# hp3547DisplayV2.net
KiCad netlist of a schematic drawn in EAGLE
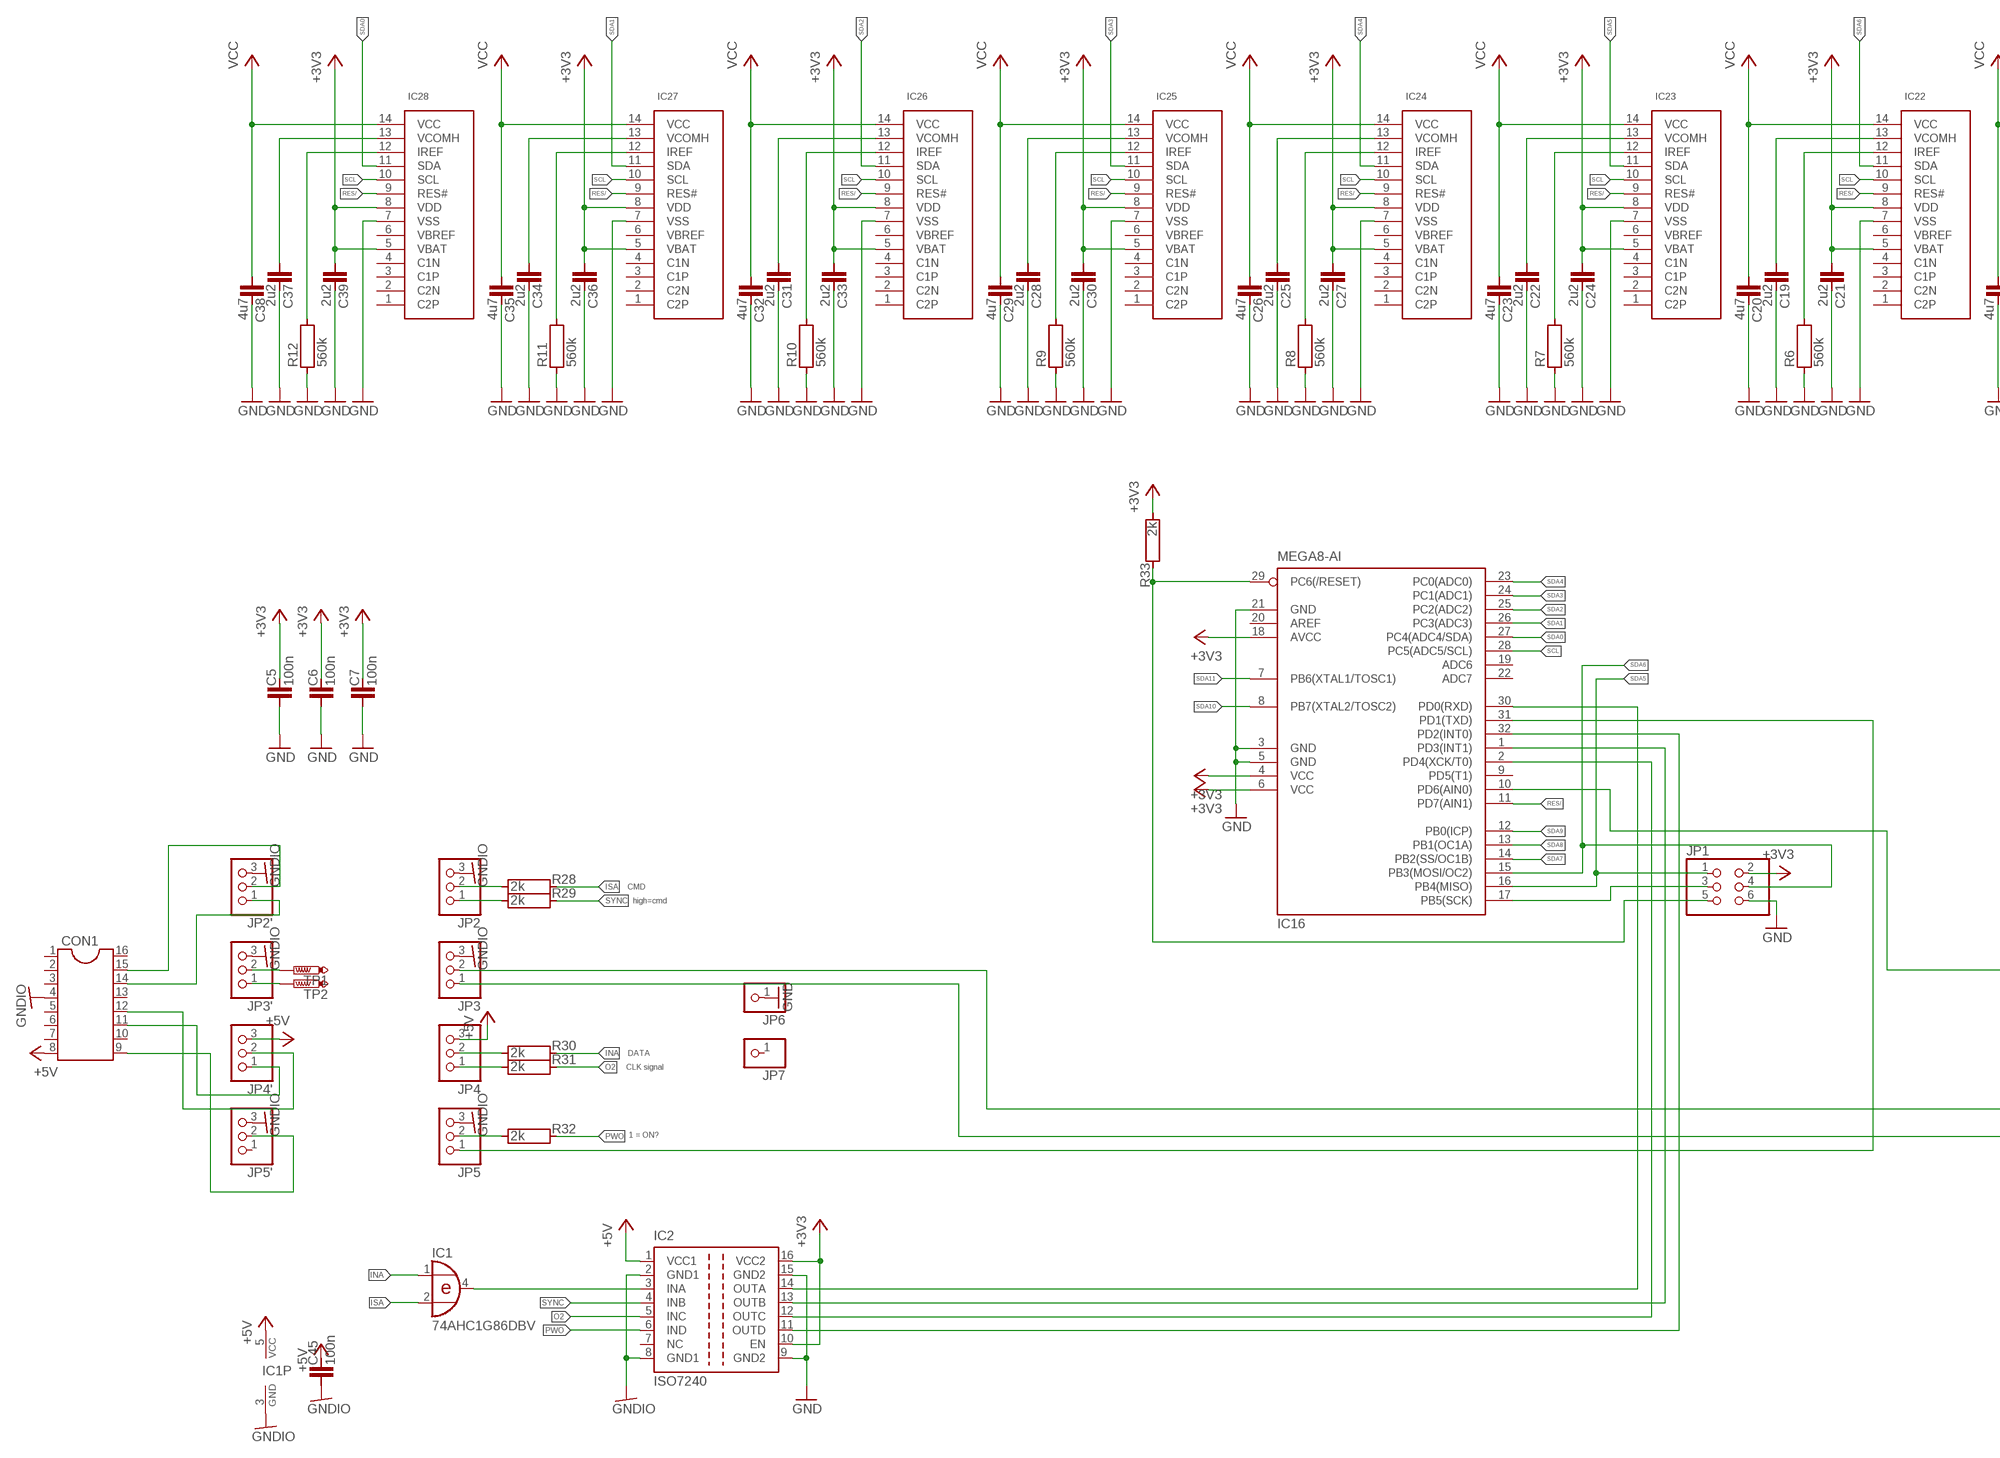
[diagram p0: schematic, sheet 1, part 1 of 2]
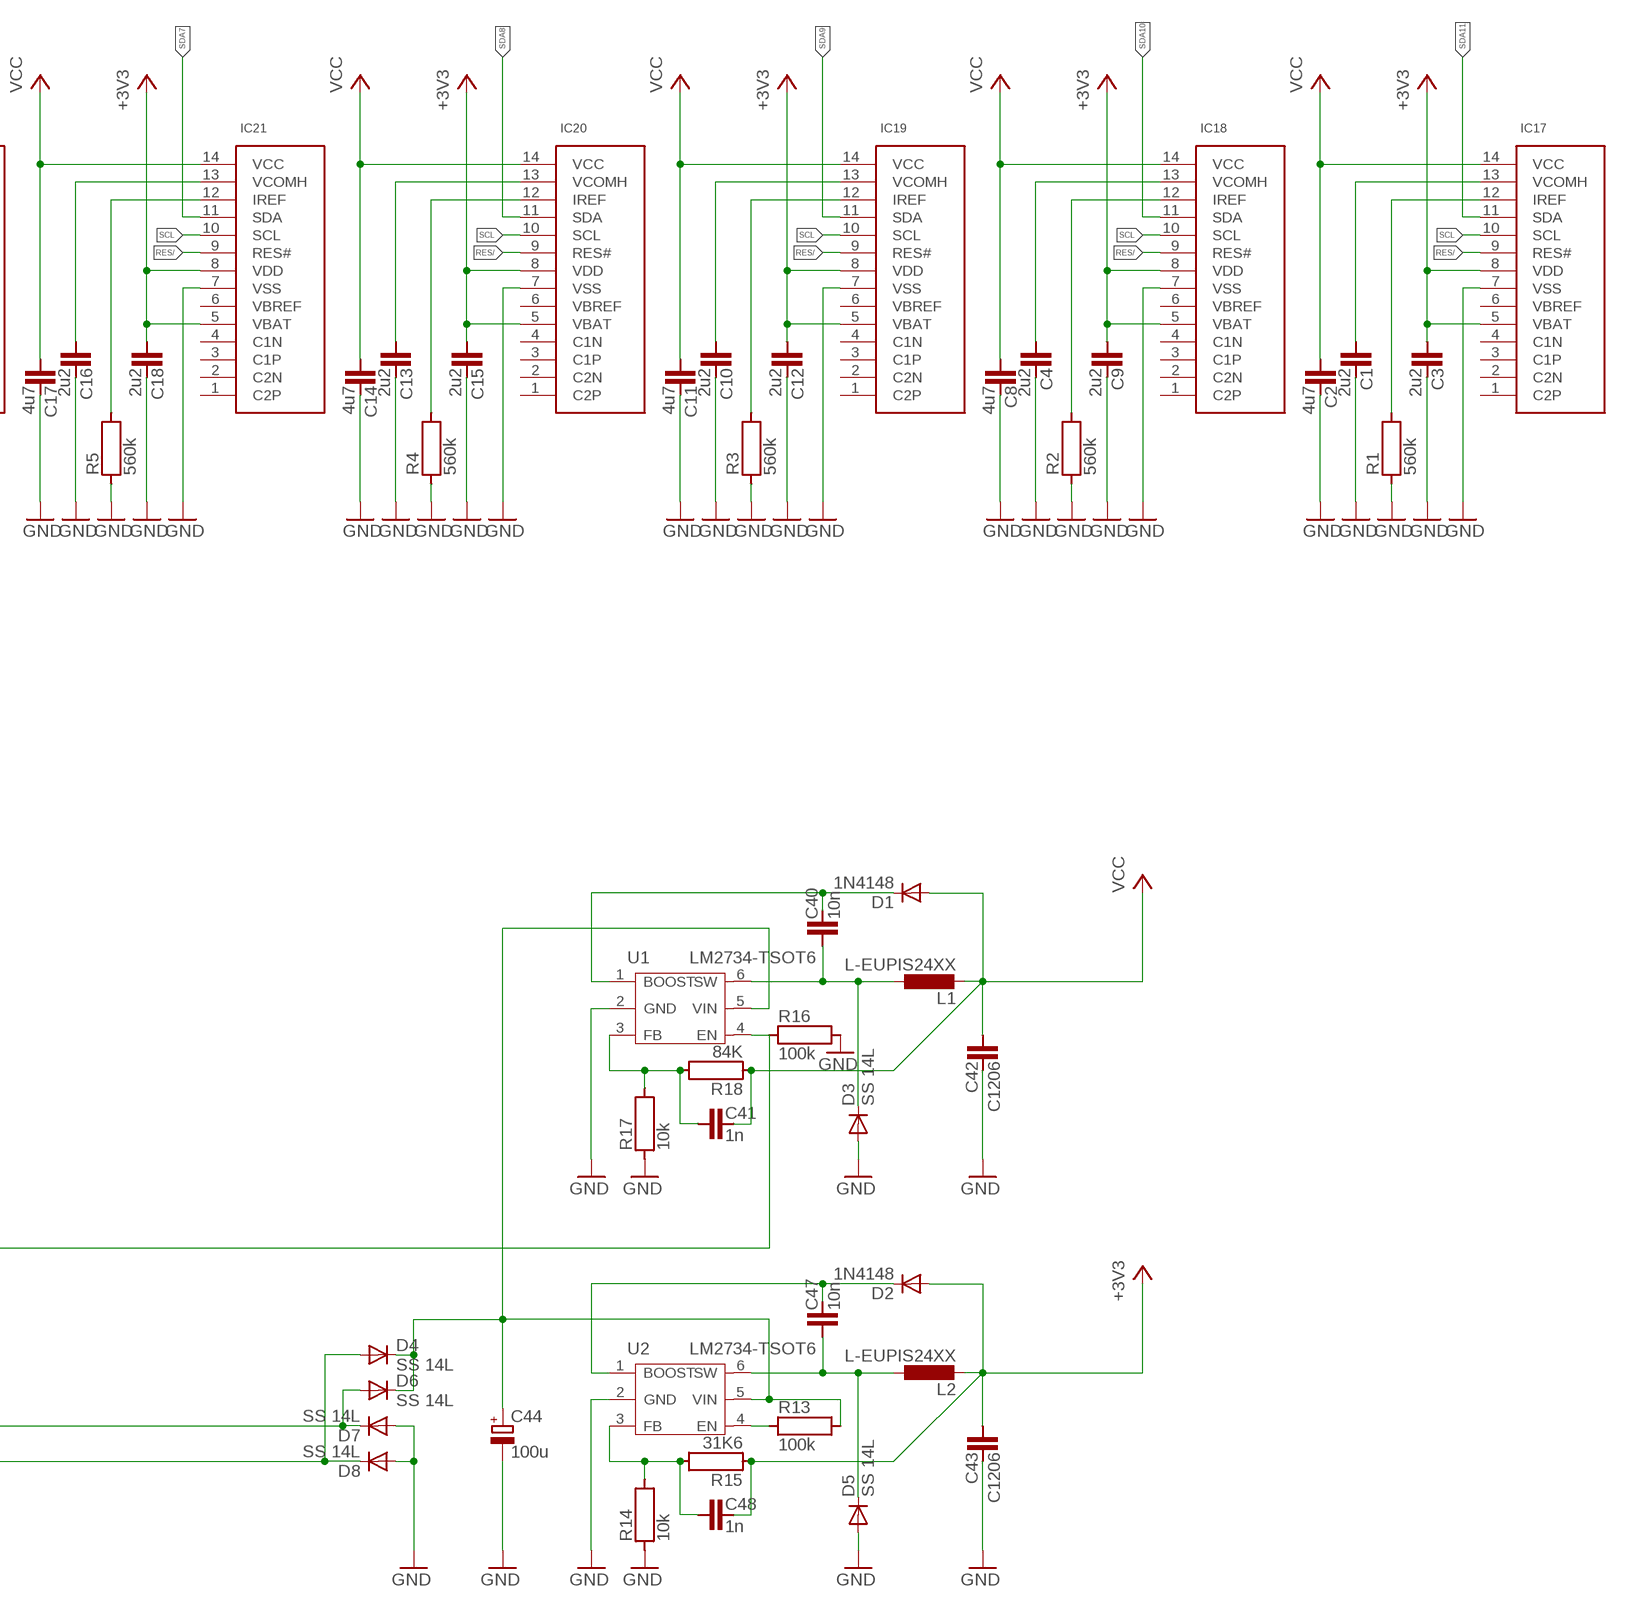
[diagram p1: schematic, sheet 1, part 2 of 2]

(export (version "E")
  (design (tool "Eeschema 10.0.6"))
  (components
    (comp (ref "C1")
      (value "2u2")
      (footprint "eagle-import:C0603")
      (libsource (lib "eagle-import") (part "C0603"))
    )
    (comp (ref "C2")
      (value "4u7")
      (footprint "eagle-import:C0805")
      (libsource (lib "eagle-import") (part "C0805"))
    )
    (comp (ref "C3")
      (value "2u2")
      (footprint "eagle-import:C0603")
      (libsource (lib "eagle-import") (part "C0603"))
    )
    (comp (ref "C4")
      (value "2u2")
      (footprint "eagle-import:C0603")
      (libsource (lib "eagle-import") (part "C0603"))
    )
    (comp (ref "C5")
      (value "100n")
      (footprint "eagle-import:C0603")
      (libsource (lib "eagle-import") (part "C0603"))
    )
    (comp (ref "C6")
      (value "100n")
      (footprint "eagle-import:C0603")
      (libsource (lib "eagle-import") (part "C0603"))
    )
    (comp (ref "C7")
      (value "100n")
      (footprint "eagle-import:C0603")
      (libsource (lib "eagle-import") (part "C0603"))
    )
    (comp (ref "C8")
      (value "4u7")
      (footprint "eagle-import:C0805")
      (libsource (lib "eagle-import") (part "C0805"))
    )
    (comp (ref "C9")
      (value "2u2")
      (footprint "eagle-import:C0603")
      (libsource (lib "eagle-import") (part "C0603"))
    )
    (comp (ref "C10")
      (value "2u2")
      (footprint "eagle-import:C0603")
      (libsource (lib "eagle-import") (part "C0603"))
    )
    (comp (ref "C11")
      (value "4u7")
      (footprint "eagle-import:C0805")
      (libsource (lib "eagle-import") (part "C0805"))
    )
    (comp (ref "C12")
      (value "2u2")
      (footprint "eagle-import:C0603")
      (libsource (lib "eagle-import") (part "C0603"))
    )
    (comp (ref "C13")
      (value "2u2")
      (footprint "eagle-import:C0603")
      (libsource (lib "eagle-import") (part "C0603"))
    )
    (comp (ref "C14")
      (value "4u7")
      (footprint "eagle-import:C0805")
      (libsource (lib "eagle-import") (part "C0805"))
    )
    (comp (ref "C15")
      (value "2u2")
      (footprint "eagle-import:C0603")
      (libsource (lib "eagle-import") (part "C0603"))
    )
    (comp (ref "C16")
      (value "2u2")
      (footprint "eagle-import:C0603")
      (libsource (lib "eagle-import") (part "C0603"))
    )
    (comp (ref "C17")
      (value "4u7")
      (footprint "eagle-import:C0805")
      (libsource (lib "eagle-import") (part "C0805"))
    )
    (comp (ref "C18")
      (value "2u2")
      (footprint "eagle-import:C0603")
      (libsource (lib "eagle-import") (part "C0603"))
    )
    (comp (ref "C19")
      (value "2u2")
      (footprint "eagle-import:C0603")
      (libsource (lib "eagle-import") (part "C0603"))
    )
    (comp (ref "C20")
      (value "4u7")
      (footprint "eagle-import:C0805")
      (libsource (lib "eagle-import") (part "C0805"))
    )
    (comp (ref "C21")
      (value "2u2")
      (footprint "eagle-import:C0603")
      (libsource (lib "eagle-import") (part "C0603"))
    )
    (comp (ref "C22")
      (value "2u2")
      (footprint "eagle-import:C0603")
      (libsource (lib "eagle-import") (part "C0603"))
    )
    (comp (ref "C23")
      (value "4u7")
      (footprint "eagle-import:C0805")
      (libsource (lib "eagle-import") (part "C0805"))
    )
    (comp (ref "C24")
      (value "2u2")
      (footprint "eagle-import:C0603")
      (libsource (lib "eagle-import") (part "C0603"))
    )
    (comp (ref "C25")
      (value "2u2")
      (footprint "eagle-import:C0603")
      (libsource (lib "eagle-import") (part "C0603"))
    )
    (comp (ref "C26")
      (value "4u7")
      (footprint "eagle-import:C0805")
      (libsource (lib "eagle-import") (part "C0805"))
    )
    (comp (ref "C27")
      (value "2u2")
      (footprint "eagle-import:C0603")
      (libsource (lib "eagle-import") (part "C0603"))
    )
    (comp (ref "C28")
      (value "2u2")
      (footprint "eagle-import:C0603")
      (libsource (lib "eagle-import") (part "C0603"))
    )
    (comp (ref "C29")
      (value "4u7")
      (footprint "eagle-import:C0805")
      (libsource (lib "eagle-import") (part "C0805"))
    )
    (comp (ref "C30")
      (value "2u2")
      (footprint "eagle-import:C0603")
      (libsource (lib "eagle-import") (part "C0603"))
    )
    (comp (ref "C31")
      (value "2u2")
      (footprint "eagle-import:C0603")
      (libsource (lib "eagle-import") (part "C0603"))
    )
    (comp (ref "C32")
      (value "4u7")
      (footprint "eagle-import:C0805")
      (libsource (lib "eagle-import") (part "C0805"))
    )
    (comp (ref "C33")
      (value "2u2")
      (footprint "eagle-import:C0603")
      (libsource (lib "eagle-import") (part "C0603"))
    )
    (comp (ref "C34")
      (value "2u2")
      (footprint "eagle-import:C0603")
      (libsource (lib "eagle-import") (part "C0603"))
    )
    (comp (ref "C35")
      (value "4u7")
      (footprint "eagle-import:C0805")
      (libsource (lib "eagle-import") (part "C0805"))
    )
    (comp (ref "C36")
      (value "2u2")
      (footprint "eagle-import:C0603")
      (libsource (lib "eagle-import") (part "C0603"))
    )
    (comp (ref "C37")
      (value "2u2")
      (footprint "eagle-import:C0603")
      (libsource (lib "eagle-import") (part "C0603"))
    )
    (comp (ref "C38")
      (value "4u7")
      (footprint "eagle-import:C0805")
      (libsource (lib "eagle-import") (part "C0805"))
    )
    (comp (ref "C39")
      (value "2u2")
      (footprint "eagle-import:C0603")
      (libsource (lib "eagle-import") (part "C0603"))
    )
    (comp (ref "C40")
      (value "10n")
      (footprint "eagle-import:C0603")
      (libsource (lib "eagle-import") (part "C0603"))
    )
    (comp (ref "C41")
      (value "1n")
      (footprint "eagle-import:C0603")
      (libsource (lib "eagle-import") (part "C0603"))
    )
    (comp (ref "C42")
      (value "C1206")
      (footprint "eagle-import:C1206")
      (libsource (lib "eagle-import") (part "C1206"))
    )
    (comp (ref "C43")
      (value "C1206")
      (footprint "eagle-import:C1206")
      (libsource (lib "eagle-import") (part "C1206"))
    )
    (comp (ref "C44")
      (value "100u")
      (footprint "eagle-import:PANASONIC_E")
      (libsource (lib "eagle-import") (part "CPOL-EUE"))
    )
    (comp (ref "C45")
      (value "100n")
      (footprint "eagle-import:C0603")
      (libsource (lib "eagle-import") (part "C0603"))
    )
    (comp (ref "C47")
      (value "10n")
      (footprint "eagle-import:C0603")
      (libsource (lib "eagle-import") (part "C0603"))
    )
    (comp (ref "C48")
      (value "1n")
      (footprint "eagle-import:C0603")
      (libsource (lib "eagle-import") (part "C0603"))
    )
    (comp (ref "CON1")
      (value "DIL16BIGHOLE")
      (footprint "eagle-import:DIL16BIGHOLE")
      (libsource (lib "eagle-import") (part "DIL16BIGHOLE"))
    )
    (comp (ref "D1")
      (value "1N4148")
      (footprint "eagle-import:DO214AC")
      (libsource (lib "eagle-import") (part "DIODE-DO214AC"))
    )
    (comp (ref "D2")
      (value "1N4148")
      (footprint "eagle-import:DO214AC")
      (libsource (lib "eagle-import") (part "DIODE-DO214AC"))
    )
    (comp (ref "D3")
      (value "SS 14L")
      (footprint "eagle-import:SOD-123_MINI-SMA")
      (libsource (lib "eagle-import") (part "CGRM400-G1"))
    )
    (comp (ref "D4")
      (value "SS 14L")
      (footprint "eagle-import:SOD-123_MINI-SMA")
      (libsource (lib "eagle-import") (part "CGRM400-G1"))
    )
    (comp (ref "D5")
      (value "SS 14L")
      (footprint "eagle-import:SOD-123_MINI-SMA")
      (libsource (lib "eagle-import") (part "CGRM400-G1"))
    )
    (comp (ref "D6")
      (value "SS 14L")
      (footprint "eagle-import:SOD-123_MINI-SMA")
      (libsource (lib "eagle-import") (part "CGRM400-G1"))
    )
    (comp (ref "D7")
      (value "SS 14L")
      (footprint "eagle-import:SOD-123_MINI-SMA")
      (libsource (lib "eagle-import") (part "CGRM400-G1"))
    )
    (comp (ref "D8")
      (value "SS 14L")
      (footprint "eagle-import:SOD-123_MINI-SMA")
      (libsource (lib "eagle-import") (part "CGRM400-G1"))
    )
    (comp (ref "IC1")
      (value "74AHC1G86DBV")
      (footprint "eagle-import:SOT23-5")
      (libsource (lib "eagle-import") (part "741G86DBVAHC"))
    )
    (comp (ref "IC2")
      (value "ISO7240")
      (footprint "eagle-import:SO-16DW")
      (fields (field (name "MPN") "ISO7240MDW"))
      (libsource (lib "eagle-import") (part "ISO7240"))
    )
    (comp (ref "IC16")
      (value "MEGA8-AI")
      (footprint "eagle-import:TQFP32-08")
      (fields (field (name "MPN") "ATMEGA8-16AU"))
      (libsource (lib "eagle-import") (part "MEGA8-AI"))
    )
    (comp (ref "IC17")
      (value "OLED0.87")
      (footprint "eagle-import:OLED0.87")
      (libsource (lib "eagle-import") (part "OLED0.87"))
    )
    (comp (ref "IC18")
      (value "OLED0.87")
      (footprint "eagle-import:OLED0.87")
      (libsource (lib "eagle-import") (part "OLED0.87"))
    )
    (comp (ref "IC19")
      (value "OLED0.87")
      (footprint "eagle-import:OLED0.87")
      (libsource (lib "eagle-import") (part "OLED0.87"))
    )
    (comp (ref "IC20")
      (value "OLED0.87")
      (footprint "eagle-import:OLED0.87")
      (libsource (lib "eagle-import") (part "OLED0.87"))
    )
    (comp (ref "IC21")
      (value "OLED0.87")
      (footprint "eagle-import:OLED0.87")
      (libsource (lib "eagle-import") (part "OLED0.87"))
    )
    (comp (ref "IC22")
      (value "OLED0.87")
      (footprint "eagle-import:OLED0.87")
      (libsource (lib "eagle-import") (part "OLED0.87"))
    )
    (comp (ref "IC23")
      (value "OLED0.87")
      (footprint "eagle-import:OLED0.87")
      (libsource (lib "eagle-import") (part "OLED0.87"))
    )
    (comp (ref "IC24")
      (value "OLED0.87")
      (footprint "eagle-import:OLED0.87")
      (libsource (lib "eagle-import") (part "OLED0.87"))
    )
    (comp (ref "IC25")
      (value "OLED0.87")
      (footprint "eagle-import:OLED0.87")
      (libsource (lib "eagle-import") (part "OLED0.87"))
    )
    (comp (ref "IC26")
      (value "OLED0.87")
      (footprint "eagle-import:OLED0.87")
      (libsource (lib "eagle-import") (part "OLED0.87"))
    )
    (comp (ref "IC27")
      (value "OLED0.87")
      (footprint "eagle-import:OLED0.87")
      (libsource (lib "eagle-import") (part "OLED0.87"))
    )
    (comp (ref "IC28")
      (value "OLED0.87")
      (footprint "eagle-import:OLED0.87")
      (libsource (lib "eagle-import") (part "OLED0.87"))
    )
    (comp (ref "JP1")
      (value "PINHD-2X3")
      (footprint "eagle-import:2X03")
      (libsource (lib "eagle-import") (part "PINHD-2X3"))
    )
    (comp (ref "JP2")
      (value "PINHD-1X3")
      (footprint "eagle-import:1X03")
      (libsource (lib "eagle-import") (part "PINHD-1X3"))
    )
    (comp (ref "JP2'")
      (value "PINHD-1X3")
      (footprint "eagle-import:1X03")
      (libsource (lib "eagle-import") (part "PINHD-1X3"))
    )
    (comp (ref "JP3")
      (value "PINHD-1X3")
      (footprint "eagle-import:1X03")
      (libsource (lib "eagle-import") (part "PINHD-1X3"))
    )
    (comp (ref "JP3'")
      (value "PINHD-1X3")
      (footprint "eagle-import:1X03")
      (libsource (lib "eagle-import") (part "PINHD-1X3"))
    )
    (comp (ref "JP4")
      (value "PINHD-1X3")
      (footprint "eagle-import:1X03")
      (libsource (lib "eagle-import") (part "PINHD-1X3"))
    )
    (comp (ref "JP4'")
      (value "PINHD-1X3")
      (footprint "eagle-import:1X03")
      (libsource (lib "eagle-import") (part "PINHD-1X3"))
    )
    (comp (ref "JP5")
      (value "PINHD-1X3")
      (footprint "eagle-import:1X03")
      (libsource (lib "eagle-import") (part "PINHD-1X3"))
    )
    (comp (ref "JP5'")
      (value "PINHD-1X3")
      (footprint "eagle-import:1X03")
      (libsource (lib "eagle-import") (part "PINHD-1X3"))
    )
    (comp (ref "JP6")
      (value "PINHD-1X1")
      (footprint "eagle-import:1X01")
      (libsource (lib "eagle-import") (part "PINHD-1X1"))
    )
    (comp (ref "JP7")
      (value "PINHD-1X1")
      (footprint "eagle-import:1X01")
      (libsource (lib "eagle-import") (part "PINHD-1X1"))
    )
    (comp (ref "L1")
      (value "L-EUPIS24XX")
      (footprint "eagle-import:PIS24XX")
      (libsource (lib "eagle-import") (part "L-EUPIS24XX"))
    )
    (comp (ref "L2")
      (value "L-EUPIS24XX")
      (footprint "eagle-import:PIS24XX")
      (libsource (lib "eagle-import") (part "L-EUPIS24XX"))
    )
    (comp (ref "R1")
      (value "560k")
      (footprint "eagle-import:R0402")
      (libsource (lib "eagle-import") (part "R0402"))
    )
    (comp (ref "R2")
      (value "560k")
      (footprint "eagle-import:R0402")
      (libsource (lib "eagle-import") (part "R0402"))
    )
    (comp (ref "R3")
      (value "560k")
      (footprint "eagle-import:R0402")
      (libsource (lib "eagle-import") (part "R0402"))
    )
    (comp (ref "R4")
      (value "560k")
      (footprint "eagle-import:R0402")
      (libsource (lib "eagle-import") (part "R0402"))
    )
    (comp (ref "R5")
      (value "560k")
      (footprint "eagle-import:R0402")
      (libsource (lib "eagle-import") (part "R0402"))
    )
    (comp (ref "R6")
      (value "560k")
      (footprint "eagle-import:R0402")
      (libsource (lib "eagle-import") (part "R0402"))
    )
    (comp (ref "R7")
      (value "560k")
      (footprint "eagle-import:R0402")
      (libsource (lib "eagle-import") (part "R0402"))
    )
    (comp (ref "R8")
      (value "560k")
      (footprint "eagle-import:R0402")
      (libsource (lib "eagle-import") (part "R0402"))
    )
    (comp (ref "R9")
      (value "560k")
      (footprint "eagle-import:R0402")
      (libsource (lib "eagle-import") (part "R0402"))
    )
    (comp (ref "R10")
      (value "560k")
      (footprint "eagle-import:R0402")
      (libsource (lib "eagle-import") (part "R0402"))
    )
    (comp (ref "R11")
      (value "560k")
      (footprint "eagle-import:R0402")
      (libsource (lib "eagle-import") (part "R0402"))
    )
    (comp (ref "R12")
      (value "560k")
      (footprint "eagle-import:R0402")
      (libsource (lib "eagle-import") (part "R0402"))
    )
    (comp (ref "R13")
      (value "100k")
      (footprint "eagle-import:R0603")
      (libsource (lib "eagle-import") (part "R0603"))
    )
    (comp (ref "R14")
      (value "10k")
      (footprint "eagle-import:R0603")
      (libsource (lib "eagle-import") (part "R0603"))
    )
    (comp (ref "R15")
      (value "31K6")
      (footprint "eagle-import:R0603")
      (libsource (lib "eagle-import") (part "R0603"))
    )
    (comp (ref "R16")
      (value "100k")
      (footprint "eagle-import:R0603")
      (libsource (lib "eagle-import") (part "R0603"))
    )
    (comp (ref "R17")
      (value "10k")
      (footprint "eagle-import:R0603")
      (libsource (lib "eagle-import") (part "R0603"))
    )
    (comp (ref "R18")
      (value "84K")
      (footprint "eagle-import:R0603")
      (libsource (lib "eagle-import") (part "R0603"))
    )
    (comp (ref "R28")
      (value "2k")
      (footprint "eagle-import:R0603")
      (libsource (lib "eagle-import") (part "R0603"))
    )
    (comp (ref "R29")
      (value "2k")
      (footprint "eagle-import:R0603")
      (libsource (lib "eagle-import") (part "R0603"))
    )
    (comp (ref "R30")
      (value "2k")
      (footprint "eagle-import:R0603")
      (libsource (lib "eagle-import") (part "R0603"))
    )
    (comp (ref "R31")
      (value "2k")
      (footprint "eagle-import:R0603")
      (libsource (lib "eagle-import") (part "R0603"))
    )
    (comp (ref "R32")
      (value "2k")
      (footprint "eagle-import:R0603")
      (libsource (lib "eagle-import") (part "R0603"))
    )
    (comp (ref "R33")
      (value "2k")
      (footprint "eagle-import:R0603")
      (libsource (lib "eagle-import") (part "R0603"))
    )
    (comp (ref "TP1")
      (value "PTR1PAD1-13Y")
      (footprint "eagle-import:P1-13Y")
      (libsource (lib "eagle-import") (part "PTR1PAD1-13Y"))
    )
    (comp (ref "TP2")
      (value "PTR1PAD1-13Y")
      (footprint "eagle-import:P1-13Y")
      (libsource (lib "eagle-import") (part "PTR1PAD1-13Y"))
    )
    (comp (ref "U1")
      (value "LM2734-TSOT6")
      (footprint "eagle-import:TSOT6")
      (libsource (lib "eagle-import") (part "LM2734-TSOT6"))
    )
    (comp (ref "U2")
      (value "LM2734-TSOT6")
      (footprint "eagle-import:TSOT6")
      (libsource (lib "eagle-import") (part "LM2734-TSOT6"))
    )
  )
  (nets
    (net (code "1") (name "+3V3") (class "Default")
      (node (ref "C12") (pin "1") (pinfunction "1_1") (pintype "passive"))
      (node (ref "C15") (pin "1") (pinfunction "1_1") (pintype "passive"))
      (node (ref "C18") (pin "1") (pinfunction "1_1") (pintype "passive"))
      (node (ref "C21") (pin "1") (pinfunction "1_1") (pintype "passive"))
      (node (ref "C24") (pin "1") (pinfunction "1_1") (pintype "passive"))
      (node (ref "C27") (pin "1") (pinfunction "1_1") (pintype "passive"))
      (node (ref "C3") (pin "1") (pinfunction "1_1") (pintype "passive"))
      (node (ref "C30") (pin "1") (pinfunction "1_1") (pintype "passive"))
      (node (ref "C33") (pin "1") (pinfunction "1_1") (pintype "passive"))
      (node (ref "C36") (pin "1") (pinfunction "1_1") (pintype "passive"))
      (node (ref "C39") (pin "1") (pinfunction "1_1") (pintype "passive"))
      (node (ref "C43") (pin "1") (pinfunction "1_1") (pintype "passive"))
      (node (ref "C48") (pin "2") (pinfunction "2_2") (pintype "passive"))
      (node (ref "C5") (pin "2") (pinfunction "2_2") (pintype "passive"))
      (node (ref "C6") (pin "2") (pinfunction "2_2") (pintype "passive"))
      (node (ref "C7") (pin "2") (pinfunction "2_2") (pintype "passive"))
      (node (ref "C9") (pin "1") (pinfunction "1_1") (pintype "passive"))
      (node (ref "D2") (pin "A") (pinfunction "A_A") (pintype "passive"))
      (node (ref "IC16") (pin "18") (pinfunction "AVCC_18") (pintype "power_in"))
      (node (ref "IC16") (pin "4") (pinfunction "VCC_4") (pintype "power_in"))
      (node (ref "IC16") (pin "6") (pinfunction "VCC_6") (pintype "power_in"))
      (node (ref "IC17") (pin "5") (pinfunction "VBAT_5") (pintype "bidirectional"))
      (node (ref "IC17") (pin "8") (pinfunction "VDD_8") (pintype "bidirectional"))
      (node (ref "IC18") (pin "5") (pinfunction "VBAT_5") (pintype "bidirectional"))
      (node (ref "IC18") (pin "8") (pinfunction "VDD_8") (pintype "bidirectional"))
      (node (ref "IC19") (pin "5") (pinfunction "VBAT_5") (pintype "bidirectional"))
      (node (ref "IC19") (pin "8") (pinfunction "VDD_8") (pintype "bidirectional"))
      (node (ref "IC2") (pin "10") (pinfunction "EN_10") (pintype "input"))
      (node (ref "IC2") (pin "16") (pinfunction "VCC2_16") (pintype "power_in"))
      (node (ref "IC20") (pin "5") (pinfunction "VBAT_5") (pintype "bidirectional"))
      (node (ref "IC20") (pin "8") (pinfunction "VDD_8") (pintype "bidirectional"))
      (node (ref "IC21") (pin "5") (pinfunction "VBAT_5") (pintype "bidirectional"))
      (node (ref "IC21") (pin "8") (pinfunction "VDD_8") (pintype "bidirectional"))
      (node (ref "IC22") (pin "5") (pinfunction "VBAT_5") (pintype "bidirectional"))
      (node (ref "IC22") (pin "8") (pinfunction "VDD_8") (pintype "bidirectional"))
      (node (ref "IC23") (pin "5") (pinfunction "VBAT_5") (pintype "bidirectional"))
      (node (ref "IC23") (pin "8") (pinfunction "VDD_8") (pintype "bidirectional"))
      (node (ref "IC24") (pin "5") (pinfunction "VBAT_5") (pintype "bidirectional"))
      (node (ref "IC24") (pin "8") (pinfunction "VDD_8") (pintype "bidirectional"))
      (node (ref "IC25") (pin "5") (pinfunction "VBAT_5") (pintype "bidirectional"))
      (node (ref "IC25") (pin "8") (pinfunction "VDD_8") (pintype "bidirectional"))
      (node (ref "IC26") (pin "5") (pinfunction "VBAT_5") (pintype "bidirectional"))
      (node (ref "IC26") (pin "8") (pinfunction "VDD_8") (pintype "bidirectional"))
      (node (ref "IC27") (pin "5") (pinfunction "VBAT_5") (pintype "bidirectional"))
      (node (ref "IC27") (pin "8") (pinfunction "VDD_8") (pintype "bidirectional"))
      (node (ref "IC28") (pin "5") (pinfunction "VBAT_5") (pintype "bidirectional"))
      (node (ref "IC28") (pin "8") (pinfunction "VDD_8") (pintype "bidirectional"))
      (node (ref "JP1") (pin "2") (pinfunction "2_2") (pintype "passive"))
      (node (ref "L2") (pin "1") (pinfunction "2_1") (pintype "passive"))
      (node (ref "R15") (pin "1") (pinfunction "1_1") (pintype "passive"))
      (node (ref "R33") (pin "2") (pinfunction "2_2") (pintype "passive"))
    )
    (net (code "2") (name "+5V") (class "Default")
      (node (ref "C45") (pin "2") (pinfunction "2_2") (pintype "passive"))
      (node (ref "CON1") (pin "8") (pinfunction "8_8") (pintype "passive"))
      (node (ref "IC1") (pin "5") (pinfunction "VCC_5") (pintype "power_in"))
      (node (ref "IC2") (pin "1") (pinfunction "VCC1_1") (pintype "power_in"))
      (node (ref "JP4") (pin "3") (pinfunction "3_3") (pintype "passive"))
      (node (ref "JP4'") (pin "3") (pinfunction "3_3") (pintype "passive"))
    )
    (net (code "3") (name "GND") (class "Default")
      (node (ref "C1") (pin "2") (pinfunction "2_2") (pintype "passive"))
      (node (ref "C10") (pin "2") (pinfunction "2_2") (pintype "passive"))
      (node (ref "C11") (pin "2") (pinfunction "2_2") (pintype "passive"))
      (node (ref "C12") (pin "2") (pinfunction "2_2") (pintype "passive"))
      (node (ref "C13") (pin "2") (pinfunction "2_2") (pintype "passive"))
      (node (ref "C14") (pin "2") (pinfunction "2_2") (pintype "passive"))
      (node (ref "C15") (pin "2") (pinfunction "2_2") (pintype "passive"))
      (node (ref "C16") (pin "2") (pinfunction "2_2") (pintype "passive"))
      (node (ref "C17") (pin "2") (pinfunction "2_2") (pintype "passive"))
      (node (ref "C18") (pin "2") (pinfunction "2_2") (pintype "passive"))
      (node (ref "C19") (pin "2") (pinfunction "2_2") (pintype "passive"))
      (node (ref "C2") (pin "2") (pinfunction "2_2") (pintype "passive"))
      (node (ref "C20") (pin "2") (pinfunction "2_2") (pintype "passive"))
      (node (ref "C21") (pin "2") (pinfunction "2_2") (pintype "passive"))
      (node (ref "C22") (pin "2") (pinfunction "2_2") (pintype "passive"))
      (node (ref "C23") (pin "2") (pinfunction "2_2") (pintype "passive"))
      (node (ref "C24") (pin "2") (pinfunction "2_2") (pintype "passive"))
      (node (ref "C25") (pin "2") (pinfunction "2_2") (pintype "passive"))
      (node (ref "C26") (pin "2") (pinfunction "2_2") (pintype "passive"))
      (node (ref "C27") (pin "2") (pinfunction "2_2") (pintype "passive"))
      (node (ref "C28") (pin "2") (pinfunction "2_2") (pintype "passive"))
      (node (ref "C29") (pin "2") (pinfunction "2_2") (pintype "passive"))
      (node (ref "C3") (pin "2") (pinfunction "2_2") (pintype "passive"))
      (node (ref "C30") (pin "2") (pinfunction "2_2") (pintype "passive"))
      (node (ref "C31") (pin "2") (pinfunction "2_2") (pintype "passive"))
      (node (ref "C32") (pin "2") (pinfunction "2_2") (pintype "passive"))
      (node (ref "C33") (pin "2") (pinfunction "2_2") (pintype "passive"))
      (node (ref "C34") (pin "2") (pinfunction "2_2") (pintype "passive"))
      (node (ref "C35") (pin "2") (pinfunction "2_2") (pintype "passive"))
      (node (ref "C36") (pin "2") (pinfunction "2_2") (pintype "passive"))
      (node (ref "C37") (pin "2") (pinfunction "2_2") (pintype "passive"))
      (node (ref "C38") (pin "2") (pinfunction "2_2") (pintype "passive"))
      (node (ref "C39") (pin "2") (pinfunction "2_2") (pintype "passive"))
      (node (ref "C4") (pin "2") (pinfunction "2_2") (pintype "passive"))
      (node (ref "C42") (pin "2") (pinfunction "2_2") (pintype "passive"))
      (node (ref "C43") (pin "2") (pinfunction "2_2") (pintype "passive"))
      (node (ref "C44") (pin "-") (pinfunction "-_-") (pintype "passive"))
      (node (ref "C5") (pin "1") (pinfunction "1_1") (pintype "passive"))
      (node (ref "C6") (pin "1") (pinfunction "1_1") (pintype "passive"))
      (node (ref "C7") (pin "1") (pinfunction "1_1") (pintype "passive"))
      (node (ref "C8") (pin "2") (pinfunction "2_2") (pintype "passive"))
      (node (ref "C9") (pin "2") (pinfunction "2_2") (pintype "passive"))
      (node (ref "D3") (pin "A") (pinfunction "A_A") (pintype "passive"))
      (node (ref "D5") (pin "A") (pinfunction "A_A") (pintype "passive"))
      (node (ref "D7") (pin "A") (pinfunction "A_A") (pintype "passive"))
      (node (ref "D8") (pin "A") (pinfunction "A_A") (pintype "passive"))
      (node (ref "IC16") (pin "21") (pinfunction "GND_21") (pintype "power_in"))
      (node (ref "IC16") (pin "3") (pinfunction "GND_3") (pintype "power_in"))
      (node (ref "IC16") (pin "5") (pinfunction "GND_5") (pintype "power_in"))
      (node (ref "IC17") (pin "7") (pinfunction "VSS_7") (pintype "bidirectional"))
      (node (ref "IC18") (pin "7") (pinfunction "VSS_7") (pintype "bidirectional"))
      (node (ref "IC19") (pin "7") (pinfunction "VSS_7") (pintype "bidirectional"))
      (node (ref "IC2") (pin "15") (pinfunction "GND2_15") (pintype "power_in"))
      (node (ref "IC2") (pin "9") (pinfunction "GND2_9") (pintype "power_in"))
      (node (ref "IC20") (pin "7") (pinfunction "VSS_7") (pintype "bidirectional"))
      (node (ref "IC21") (pin "7") (pinfunction "VSS_7") (pintype "bidirectional"))
      (node (ref "IC22") (pin "7") (pinfunction "VSS_7") (pintype "bidirectional"))
      (node (ref "IC23") (pin "7") (pinfunction "VSS_7") (pintype "bidirectional"))
      (node (ref "IC24") (pin "7") (pinfunction "VSS_7") (pintype "bidirectional"))
      (node (ref "IC25") (pin "7") (pinfunction "VSS_7") (pintype "bidirectional"))
      (node (ref "IC26") (pin "7") (pinfunction "VSS_7") (pintype "bidirectional"))
      (node (ref "IC27") (pin "7") (pinfunction "VSS_7") (pintype "bidirectional"))
      (node (ref "IC28") (pin "7") (pinfunction "VSS_7") (pintype "bidirectional"))
      (node (ref "JP1") (pin "6") (pinfunction "6_6") (pintype "passive"))
      (node (ref "JP6") (pin "1") (pinfunction "1_1") (pintype "passive"))
      (node (ref "R1") (pin "1") (pinfunction "1_1") (pintype "passive"))
      (node (ref "R10") (pin "1") (pinfunction "1_1") (pintype "passive"))
      (node (ref "R11") (pin "1") (pinfunction "1_1") (pintype "passive"))
      (node (ref "R12") (pin "1") (pinfunction "1_1") (pintype "passive"))
      (node (ref "R14") (pin "1") (pinfunction "1_1") (pintype "passive"))
      (node (ref "R16") (pin "2") (pinfunction "2_2") (pintype "passive"))
      (node (ref "R17") (pin "1") (pinfunction "1_1") (pintype "passive"))
      (node (ref "R2") (pin "1") (pinfunction "1_1") (pintype "passive"))
      (node (ref "R3") (pin "1") (pinfunction "1_1") (pintype "passive"))
      (node (ref "R4") (pin "1") (pinfunction "1_1") (pintype "passive"))
      (node (ref "R5") (pin "1") (pinfunction "1_1") (pintype "passive"))
      (node (ref "R6") (pin "1") (pinfunction "1_1") (pintype "passive"))
      (node (ref "R7") (pin "1") (pinfunction "1_1") (pintype "passive"))
      (node (ref "R8") (pin "1") (pinfunction "1_1") (pintype "passive"))
      (node (ref "R9") (pin "1") (pinfunction "1_1") (pintype "passive"))
      (node (ref "U1") (pin "2") (pinfunction "GND_2") (pintype "power_in"))
      (node (ref "U2") (pin "2") (pinfunction "GND_2") (pintype "power_in"))
    )
    (net (code "4") (name "GNDIO") (class "Default")
      (node (ref "C45") (pin "1") (pinfunction "1_1") (pintype "passive"))
      (node (ref "CON1") (pin "4") (pinfunction "4_4") (pintype "passive"))
      (node (ref "IC1") (pin "3") (pinfunction "GND_3") (pintype "power_in"))
      (node (ref "IC2") (pin "2") (pinfunction "GND1_2") (pintype "power_in"))
      (node (ref "IC2") (pin "8") (pinfunction "GND1_8") (pintype "power_in"))
      (node (ref "JP2") (pin "3") (pinfunction "3_3") (pintype "passive"))
      (node (ref "JP2'") (pin "3") (pinfunction "3_3") (pintype "passive"))
      (node (ref "JP3") (pin "3") (pinfunction "3_3") (pintype "passive"))
      (node (ref "JP3'") (pin "3") (pinfunction "3_3") (pintype "passive"))
      (node (ref "JP5") (pin "3") (pinfunction "3_3") (pintype "passive"))
      (node (ref "JP5'") (pin "3") (pinfunction "3_3") (pintype "passive"))
    )
    (net (code "5") (name "INA") (class "Default")
      (node (ref "IC1") (pin "1") (pinfunction "I0_1") (pintype "input"))
      (node (ref "R30") (pin "1") (pinfunction "1_1") (pintype "passive"))
    )
    (net (code "6") (name "ISA") (class "Default")
      (node (ref "IC1") (pin "2") (pinfunction "I1_2") (pintype "input"))
      (node (ref "R28") (pin "1") (pinfunction "1_1") (pintype "passive"))
    )
    (net (code "7") (name "Net-(CON1-Pad9)") (class "Default")
      (node (ref "CON1") (pin "9") (pinfunction "9_9") (pintype "passive"))
      (node (ref "JP5'") (pin "2") (pinfunction "2_2") (pintype "passive"))
    )
    (net (code "8") (name "Net-(CON1-Pad11)") (class "Default")
      (node (ref "CON1") (pin "11") (pinfunction "11_11") (pintype "passive"))
      (node (ref "JP4'") (pin "1") (pinfunction "1_1") (pintype "passive"))
    )
    (net (code "9") (name "Net-(CON1-Pad12)") (class "Default")
      (node (ref "CON1") (pin "12") (pinfunction "12_12") (pintype "passive"))
      (node (ref "JP4'") (pin "2") (pinfunction "2_2") (pintype "passive"))
    )
    (net (code "10") (name "Net-(CON1-Pad14)") (class "Default")
      (node (ref "CON1") (pin "14") (pinfunction "14_14") (pintype "passive"))
      (node (ref "JP2'") (pin "1") (pinfunction "1_1") (pintype "passive"))
    )
    (net (code "11") (name "Net-(CON1-Pad15)") (class "Default")
      (node (ref "CON1") (pin "15") (pinfunction "15_15") (pintype "passive"))
      (node (ref "JP2'") (pin "2") (pinfunction "2_2") (pintype "passive"))
    )
    (net (code "12") (name "Net-(D4-PadA)") (class "Default")
      (node (ref "D4") (pin "A") (pinfunction "A_A") (pintype "passive"))
      (node (ref "D8") (pin "C") (pinfunction "C_C") (pintype "passive"))
      (node (ref "JP3") (pin "1") (pinfunction "1_1") (pintype "passive"))
    )
    (net (code "13") (name "Net-(D6-PadA)") (class "Default")
      (node (ref "D6") (pin "A") (pinfunction "A_A") (pintype "passive"))
      (node (ref "D7") (pin "C") (pinfunction "C_C") (pintype "passive"))
      (node (ref "JP3") (pin "2") (pinfunction "2_2") (pintype "passive"))
    )
    (net (code "14") (name "Net-(IC1A-O)") (class "Default")
      (node (ref "IC1") (pin "4") (pinfunction "O_4") (pintype "output"))
      (node (ref "IC2") (pin "3") (pinfunction "INA_3") (pintype "input"))
    )
    (net (code "15") (name "Net-(IC16-PB5(SCK))") (class "Default")
      (node (ref "IC16") (pin "17") (pinfunction "PB5(SCK)_17") (pintype "bidirectional"))
      (node (ref "JP1") (pin "3") (pinfunction "3_3") (pintype "passive"))
    )
    (net (code "16") (name "Net-(IC16-PC6({slash}RESET))") (class "Default")
      (node (ref "IC16") (pin "29") (pinfunction "PC6(/RESET)_29") (pintype "bidirectional"))
      (node (ref "JP1") (pin "5") (pinfunction "5_5") (pintype "passive"))
      (node (ref "R33") (pin "1") (pinfunction "1_1") (pintype "passive"))
    )
    (net (code "17") (name "Net-(IC16-PD0(RXD))") (class "Default")
      (node (ref "IC16") (pin "30") (pinfunction "PD0(RXD)_30") (pintype "bidirectional"))
      (node (ref "IC2") (pin "14") (pinfunction "OUTA_14") (pintype "output"))
    )
    (net (code "18") (name "Net-(IC16-PD1(TXD))") (class "Default")
      (node (ref "IC16") (pin "31") (pinfunction "PD1(TXD)_31") (pintype "bidirectional"))
      (node (ref "JP5") (pin "1") (pinfunction "1_1") (pintype "passive"))
    )
    (net (code "19") (name "Net-(IC16-PD2(INT0))") (class "Default")
      (node (ref "IC16") (pin "32") (pinfunction "PD2(INT0)_32") (pintype "bidirectional"))
      (node (ref "IC2") (pin "11") (pinfunction "OUTD_11") (pintype "output"))
    )
    (net (code "20") (name "Net-(IC16-PD3(INT1))") (class "Default")
      (node (ref "IC16") (pin "1") (pinfunction "PD3(INT1)_1") (pintype "bidirectional"))
      (node (ref "IC2") (pin "13") (pinfunction "OUTB_13") (pintype "output"))
    )
    (net (code "21") (name "Net-(IC16-PD4(XCK{slash}T0))") (class "Default")
      (node (ref "IC16") (pin "2") (pinfunction "PD4(XCK/T0)_2") (pintype "bidirectional"))
      (node (ref "IC2") (pin "12") (pinfunction "OUTC_12") (pintype "output"))
    )
    (net (code "22") (name "Net-(IC16-PD6(AIN0))") (class "Default")
      (node (ref "IC16") (pin "10") (pinfunction "PD6(AIN0)_10") (pintype "bidirectional"))
      (node (ref "R16") (pin "1") (pinfunction "1_1") (pintype "passive"))
      (node (ref "U1") (pin "4") (pinfunction "EN_4") (pintype "input"))
    )
    (net (code "23") (name "Net-(IC17-IREF)") (class "Default")
      (node (ref "IC17") (pin "12") (pinfunction "IREF_12") (pintype "bidirectional"))
      (node (ref "R1") (pin "2") (pinfunction "2_2") (pintype "passive"))
    )
    (net (code "24") (name "Net-(IC17-VCOMH)") (class "Default")
      (node (ref "C1") (pin "1") (pinfunction "1_1") (pintype "passive"))
      (node (ref "IC17") (pin "13") (pinfunction "VCOMH_13") (pintype "bidirectional"))
    )
    (net (code "25") (name "Net-(IC18-IREF)") (class "Default")
      (node (ref "IC18") (pin "12") (pinfunction "IREF_12") (pintype "bidirectional"))
      (node (ref "R2") (pin "2") (pinfunction "2_2") (pintype "passive"))
    )
    (net (code "26") (name "Net-(IC18-VCOMH)") (class "Default")
      (node (ref "C4") (pin "1") (pinfunction "1_1") (pintype "passive"))
      (node (ref "IC18") (pin "13") (pinfunction "VCOMH_13") (pintype "bidirectional"))
    )
    (net (code "27") (name "Net-(IC19-IREF)") (class "Default")
      (node (ref "IC19") (pin "12") (pinfunction "IREF_12") (pintype "bidirectional"))
      (node (ref "R3") (pin "2") (pinfunction "2_2") (pintype "passive"))
    )
    (net (code "28") (name "Net-(IC19-VCOMH)") (class "Default")
      (node (ref "C10") (pin "1") (pinfunction "1_1") (pintype "passive"))
      (node (ref "IC19") (pin "13") (pinfunction "VCOMH_13") (pintype "bidirectional"))
    )
    (net (code "29") (name "Net-(IC20-IREF)") (class "Default")
      (node (ref "IC20") (pin "12") (pinfunction "IREF_12") (pintype "bidirectional"))
      (node (ref "R4") (pin "2") (pinfunction "2_2") (pintype "passive"))
    )
    (net (code "30") (name "Net-(IC20-VCOMH)") (class "Default")
      (node (ref "C13") (pin "1") (pinfunction "1_1") (pintype "passive"))
      (node (ref "IC20") (pin "13") (pinfunction "VCOMH_13") (pintype "bidirectional"))
    )
    (net (code "31") (name "Net-(IC21-IREF)") (class "Default")
      (node (ref "IC21") (pin "12") (pinfunction "IREF_12") (pintype "bidirectional"))
      (node (ref "R5") (pin "2") (pinfunction "2_2") (pintype "passive"))
    )
    (net (code "32") (name "Net-(IC21-VCOMH)") (class "Default")
      (node (ref "C16") (pin "1") (pinfunction "1_1") (pintype "passive"))
      (node (ref "IC21") (pin "13") (pinfunction "VCOMH_13") (pintype "bidirectional"))
    )
    (net (code "33") (name "Net-(IC22-IREF)") (class "Default")
      (node (ref "IC22") (pin "12") (pinfunction "IREF_12") (pintype "bidirectional"))
      (node (ref "R6") (pin "2") (pinfunction "2_2") (pintype "passive"))
    )
    (net (code "34") (name "Net-(IC22-VCOMH)") (class "Default")
      (node (ref "C19") (pin "1") (pinfunction "1_1") (pintype "passive"))
      (node (ref "IC22") (pin "13") (pinfunction "VCOMH_13") (pintype "bidirectional"))
    )
    (net (code "35") (name "Net-(IC23-IREF)") (class "Default")
      (node (ref "IC23") (pin "12") (pinfunction "IREF_12") (pintype "bidirectional"))
      (node (ref "R7") (pin "2") (pinfunction "2_2") (pintype "passive"))
    )
    (net (code "36") (name "Net-(IC23-VCOMH)") (class "Default")
      (node (ref "C22") (pin "1") (pinfunction "1_1") (pintype "passive"))
      (node (ref "IC23") (pin "13") (pinfunction "VCOMH_13") (pintype "bidirectional"))
    )
    (net (code "37") (name "Net-(IC24-IREF)") (class "Default")
      (node (ref "IC24") (pin "12") (pinfunction "IREF_12") (pintype "bidirectional"))
      (node (ref "R8") (pin "2") (pinfunction "2_2") (pintype "passive"))
    )
    (net (code "38") (name "Net-(IC24-VCOMH)") (class "Default")
      (node (ref "C25") (pin "1") (pinfunction "1_1") (pintype "passive"))
      (node (ref "IC24") (pin "13") (pinfunction "VCOMH_13") (pintype "bidirectional"))
    )
    (net (code "39") (name "Net-(IC25-IREF)") (class "Default")
      (node (ref "IC25") (pin "12") (pinfunction "IREF_12") (pintype "bidirectional"))
      (node (ref "R9") (pin "2") (pinfunction "2_2") (pintype "passive"))
    )
    (net (code "40") (name "Net-(IC25-VCOMH)") (class "Default")
      (node (ref "C28") (pin "1") (pinfunction "1_1") (pintype "passive"))
      (node (ref "IC25") (pin "13") (pinfunction "VCOMH_13") (pintype "bidirectional"))
    )
    (net (code "41") (name "Net-(IC26-IREF)") (class "Default")
      (node (ref "IC26") (pin "12") (pinfunction "IREF_12") (pintype "bidirectional"))
      (node (ref "R10") (pin "2") (pinfunction "2_2") (pintype "passive"))
    )
    (net (code "42") (name "Net-(IC26-VCOMH)") (class "Default")
      (node (ref "C31") (pin "1") (pinfunction "1_1") (pintype "passive"))
      (node (ref "IC26") (pin "13") (pinfunction "VCOMH_13") (pintype "bidirectional"))
    )
    (net (code "43") (name "Net-(IC27-IREF)") (class "Default")
      (node (ref "IC27") (pin "12") (pinfunction "IREF_12") (pintype "bidirectional"))
      (node (ref "R11") (pin "2") (pinfunction "2_2") (pintype "passive"))
    )
    (net (code "44") (name "Net-(IC27-VCOMH)") (class "Default")
      (node (ref "C34") (pin "1") (pinfunction "1_1") (pintype "passive"))
      (node (ref "IC27") (pin "13") (pinfunction "VCOMH_13") (pintype "bidirectional"))
    )
    (net (code "45") (name "Net-(IC28-IREF)") (class "Default")
      (node (ref "IC28") (pin "12") (pinfunction "IREF_12") (pintype "bidirectional"))
      (node (ref "R12") (pin "2") (pinfunction "2_2") (pintype "passive"))
    )
    (net (code "46") (name "Net-(IC28-VCOMH)") (class "Default")
      (node (ref "C37") (pin "1") (pinfunction "1_1") (pintype "passive"))
      (node (ref "IC28") (pin "13") (pinfunction "VCOMH_13") (pintype "bidirectional"))
    )
    (net (code "47") (name "Net-(JP2-Pad1)") (class "Default")
      (node (ref "JP2") (pin "1") (pinfunction "1_1") (pintype "passive"))
      (node (ref "R29") (pin "2") (pinfunction "2_2") (pintype "passive"))
    )
    (net (code "48") (name "Net-(JP2-Pad2)") (class "Default")
      (node (ref "JP2") (pin "2") (pinfunction "2_2") (pintype "passive"))
      (node (ref "R28") (pin "2") (pinfunction "2_2") (pintype "passive"))
    )
    (net (code "49") (name "Net-(JP3'-Pad1)") (class "Default")
      (node (ref "JP3'") (pin "1") (pinfunction "1_1") (pintype "passive"))
      (node (ref "TP2") (pin "TP") (pinfunction "TP_TP") (pintype "input"))
    )
    (net (code "50") (name "Net-(JP3'-Pad2)") (class "Default")
      (node (ref "JP3'") (pin "2") (pinfunction "2_2") (pintype "passive"))
      (node (ref "TP1") (pin "TP") (pinfunction "TP_TP") (pintype "input"))
    )
    (net (code "51") (name "Net-(JP4-Pad1)") (class "Default")
      (node (ref "JP4") (pin "1") (pinfunction "1_1") (pintype "passive"))
      (node (ref "R31") (pin "2") (pinfunction "2_2") (pintype "passive"))
    )
    (net (code "52") (name "Net-(JP4-Pad2)") (class "Default")
      (node (ref "JP4") (pin "2") (pinfunction "2_2") (pintype "passive"))
      (node (ref "R30") (pin "2") (pinfunction "2_2") (pintype "passive"))
    )
    (net (code "53") (name "Net-(JP5-Pad2)") (class "Default")
      (node (ref "JP5") (pin "2") (pinfunction "2_2") (pintype "passive"))
      (node (ref "R32") (pin "2") (pinfunction "2_2") (pintype "passive"))
    )
    (net (code "54") (name "Net-(L1-1)") (class "Default")
      (node (ref "C40") (pin "1") (pinfunction "1_1") (pintype "passive"))
      (node (ref "D3") (pin "C") (pinfunction "C_C") (pintype "passive"))
      (node (ref "L1") (pin "2") (pinfunction "1_2") (pintype "passive"))
      (node (ref "U1") (pin "6") (pinfunction "SW_6") (pintype "output"))
    )
    (net (code "55") (name "Net-(L2-1)") (class "Default")
      (node (ref "C47") (pin "1") (pinfunction "1_1") (pintype "passive"))
      (node (ref "D5") (pin "C") (pinfunction "C_C") (pintype "passive"))
      (node (ref "L2") (pin "2") (pinfunction "1_2") (pintype "passive"))
      (node (ref "U2") (pin "6") (pinfunction "SW_6") (pintype "output"))
    )
    (net (code "56") (name "Net-(U1-BOOST)") (class "Default")
      (node (ref "C40") (pin "2") (pinfunction "2_2") (pintype "passive"))
      (node (ref "D1") (pin "C") (pinfunction "C_C") (pintype "passive"))
      (node (ref "U1") (pin "1") (pinfunction "BOOST_1") (pintype "input"))
    )
    (net (code "57") (name "Net-(U1-FB)") (class "Default")
      (node (ref "C41") (pin "1") (pinfunction "1_1") (pintype "passive"))
      (node (ref "R17") (pin "2") (pinfunction "2_2") (pintype "passive"))
      (node (ref "R18") (pin "2") (pinfunction "2_2") (pintype "passive"))
      (node (ref "U1") (pin "3") (pinfunction "FB_3") (pintype "input"))
    )
    (net (code "58") (name "Net-(U1-VIN)") (class "Default")
      (node (ref "C44") (pin "+") (pinfunction "+_+") (pintype "passive"))
      (node (ref "D4") (pin "C") (pinfunction "C_C") (pintype "passive"))
      (node (ref "D6") (pin "C") (pinfunction "C_C") (pintype "passive"))
      (node (ref "R13") (pin "2") (pinfunction "2_2") (pintype "passive"))
      (node (ref "U1") (pin "5") (pinfunction "VIN_5") (pintype "power_in"))
      (node (ref "U2") (pin "5") (pinfunction "VIN_5") (pintype "power_in"))
    )
    (net (code "59") (name "Net-(U2-BOOST)") (class "Default")
      (node (ref "C47") (pin "2") (pinfunction "2_2") (pintype "passive"))
      (node (ref "D2") (pin "C") (pinfunction "C_C") (pintype "passive"))
      (node (ref "U2") (pin "1") (pinfunction "BOOST_1") (pintype "input"))
    )
    (net (code "60") (name "Net-(U2-EN)") (class "Default")
      (node (ref "R13") (pin "1") (pinfunction "1_1") (pintype "passive"))
      (node (ref "U2") (pin "4") (pinfunction "EN_4") (pintype "input"))
    )
    (net (code "61") (name "Net-(U2-FB)") (class "Default")
      (node (ref "C48") (pin "1") (pinfunction "1_1") (pintype "passive"))
      (node (ref "R14") (pin "2") (pinfunction "2_2") (pintype "passive"))
      (node (ref "R15") (pin "2") (pinfunction "2_2") (pintype "passive"))
      (node (ref "U2") (pin "3") (pinfunction "FB_3") (pintype "input"))
    )
    (net (code "62") (name "O2") (class "Default")
      (node (ref "IC2") (pin "5") (pinfunction "INC_5") (pintype "input"))
      (node (ref "R31") (pin "1") (pinfunction "1_1") (pintype "passive"))
    )
    (net (code "63") (name "PWO") (class "Default")
      (node (ref "IC2") (pin "6") (pinfunction "IND_6") (pintype "input"))
      (node (ref "R32") (pin "1") (pinfunction "1_1") (pintype "passive"))
    )
    (net (code "64") (name "RES{slash}") (class "Default")
      (node (ref "IC16") (pin "11") (pinfunction "PD7(AIN1)_11") (pintype "bidirectional"))
      (node (ref "IC17") (pin "9") (pinfunction "RES#_9") (pintype "bidirectional"))
      (node (ref "IC18") (pin "9") (pinfunction "RES#_9") (pintype "bidirectional"))
      (node (ref "IC19") (pin "9") (pinfunction "RES#_9") (pintype "bidirectional"))
      (node (ref "IC20") (pin "9") (pinfunction "RES#_9") (pintype "bidirectional"))
      (node (ref "IC21") (pin "9") (pinfunction "RES#_9") (pintype "bidirectional"))
      (node (ref "IC22") (pin "9") (pinfunction "RES#_9") (pintype "bidirectional"))
      (node (ref "IC23") (pin "9") (pinfunction "RES#_9") (pintype "bidirectional"))
      (node (ref "IC24") (pin "9") (pinfunction "RES#_9") (pintype "bidirectional"))
      (node (ref "IC25") (pin "9") (pinfunction "RES#_9") (pintype "bidirectional"))
      (node (ref "IC26") (pin "9") (pinfunction "RES#_9") (pintype "bidirectional"))
      (node (ref "IC27") (pin "9") (pinfunction "RES#_9") (pintype "bidirectional"))
      (node (ref "IC28") (pin "9") (pinfunction "RES#_9") (pintype "bidirectional"))
    )
    (net (code "65") (name "SCL") (class "Default")
      (node (ref "IC16") (pin "28") (pinfunction "PC5(ADC5/SCL)_28") (pintype "bidirectional"))
      (node (ref "IC17") (pin "10") (pinfunction "SCL_10") (pintype "bidirectional"))
      (node (ref "IC18") (pin "10") (pinfunction "SCL_10") (pintype "bidirectional"))
      (node (ref "IC19") (pin "10") (pinfunction "SCL_10") (pintype "bidirectional"))
      (node (ref "IC20") (pin "10") (pinfunction "SCL_10") (pintype "bidirectional"))
      (node (ref "IC21") (pin "10") (pinfunction "SCL_10") (pintype "bidirectional"))
      (node (ref "IC22") (pin "10") (pinfunction "SCL_10") (pintype "bidirectional"))
      (node (ref "IC23") (pin "10") (pinfunction "SCL_10") (pintype "bidirectional"))
      (node (ref "IC24") (pin "10") (pinfunction "SCL_10") (pintype "bidirectional"))
      (node (ref "IC25") (pin "10") (pinfunction "SCL_10") (pintype "bidirectional"))
      (node (ref "IC26") (pin "10") (pinfunction "SCL_10") (pintype "bidirectional"))
      (node (ref "IC27") (pin "10") (pinfunction "SCL_10") (pintype "bidirectional"))
      (node (ref "IC28") (pin "10") (pinfunction "SCL_10") (pintype "bidirectional"))
    )
    (net (code "66") (name "SDA0") (class "Default")
      (node (ref "IC16") (pin "27") (pinfunction "PC4(ADC4/SDA)_27") (pintype "bidirectional"))
      (node (ref "IC28") (pin "11") (pinfunction "SDA_11") (pintype "bidirectional"))
    )
    (net (code "67") (name "SDA1") (class "Default")
      (node (ref "IC16") (pin "26") (pinfunction "PC3(ADC3)_26") (pintype "bidirectional"))
      (node (ref "IC27") (pin "11") (pinfunction "SDA_11") (pintype "bidirectional"))
    )
    (net (code "68") (name "SDA2") (class "Default")
      (node (ref "IC16") (pin "25") (pinfunction "PC2(ADC2)_25") (pintype "bidirectional"))
      (node (ref "IC26") (pin "11") (pinfunction "SDA_11") (pintype "bidirectional"))
    )
    (net (code "69") (name "SDA3") (class "Default")
      (node (ref "IC16") (pin "24") (pinfunction "PC1(ADC1)_24") (pintype "bidirectional"))
      (node (ref "IC25") (pin "11") (pinfunction "SDA_11") (pintype "bidirectional"))
    )
    (net (code "70") (name "SDA4") (class "Default")
      (node (ref "IC16") (pin "23") (pinfunction "PC0(ADC0)_23") (pintype "bidirectional"))
      (node (ref "IC24") (pin "11") (pinfunction "SDA_11") (pintype "bidirectional"))
    )
    (net (code "71") (name "SDA5") (class "Default")
      (node (ref "IC16") (pin "16") (pinfunction "PB4(MISO)_16") (pintype "bidirectional"))
      (node (ref "IC23") (pin "11") (pinfunction "SDA_11") (pintype "bidirectional"))
      (node (ref "JP1") (pin "1") (pinfunction "1_1") (pintype "passive"))
    )
    (net (code "72") (name "SDA6") (class "Default")
      (node (ref "IC16") (pin "15") (pinfunction "PB3(MOSI/OC2)_15") (pintype "bidirectional"))
      (node (ref "IC22") (pin "11") (pinfunction "SDA_11") (pintype "bidirectional"))
      (node (ref "JP1") (pin "4") (pinfunction "4_4") (pintype "passive"))
    )
    (net (code "73") (name "SDA7") (class "Default")
      (node (ref "IC16") (pin "14") (pinfunction "PB2(SS/OC1B)_14") (pintype "bidirectional"))
      (node (ref "IC21") (pin "11") (pinfunction "SDA_11") (pintype "bidirectional"))
    )
    (net (code "74") (name "SDA8") (class "Default")
      (node (ref "IC16") (pin "13") (pinfunction "PB1(OC1A)_13") (pintype "bidirectional"))
      (node (ref "IC20") (pin "11") (pinfunction "SDA_11") (pintype "bidirectional"))
    )
    (net (code "75") (name "SDA9") (class "Default")
      (node (ref "IC16") (pin "12") (pinfunction "PB0(ICP)_12") (pintype "bidirectional"))
      (node (ref "IC19") (pin "11") (pinfunction "SDA_11") (pintype "bidirectional"))
    )
    (net (code "76") (name "SDA10") (class "Default")
      (node (ref "IC16") (pin "8") (pinfunction "PB7(XTAL2/TOSC2)_8") (pintype "bidirectional"))
      (node (ref "IC18") (pin "11") (pinfunction "SDA_11") (pintype "bidirectional"))
    )
    (net (code "77") (name "SDA11") (class "Default")
      (node (ref "IC16") (pin "7") (pinfunction "PB6(XTAL1/TOSC1)_7") (pintype "bidirectional"))
      (node (ref "IC17") (pin "11") (pinfunction "SDA_11") (pintype "bidirectional"))
    )
    (net (code "78") (name "SYNC") (class "Default")
      (node (ref "IC2") (pin "4") (pinfunction "INB_4") (pintype "input"))
      (node (ref "R29") (pin "1") (pinfunction "1_1") (pintype "passive"))
    )
    (net (code "79") (name "VCC") (class "Default")
      (node (ref "C11") (pin "1") (pinfunction "1_1") (pintype "passive"))
      (node (ref "C14") (pin "1") (pinfunction "1_1") (pintype "passive"))
      (node (ref "C17") (pin "1") (pinfunction "1_1") (pintype "passive"))
      (node (ref "C2") (pin "1") (pinfunction "1_1") (pintype "passive"))
      (node (ref "C20") (pin "1") (pinfunction "1_1") (pintype "passive"))
      (node (ref "C23") (pin "1") (pinfunction "1_1") (pintype "passive"))
      (node (ref "C26") (pin "1") (pinfunction "1_1") (pintype "passive"))
      (node (ref "C29") (pin "1") (pinfunction "1_1") (pintype "passive"))
      (node (ref "C32") (pin "1") (pinfunction "1_1") (pintype "passive"))
      (node (ref "C35") (pin "1") (pinfunction "1_1") (pintype "passive"))
      (node (ref "C38") (pin "1") (pinfunction "1_1") (pintype "passive"))
      (node (ref "C41") (pin "2") (pinfunction "2_2") (pintype "passive"))
      (node (ref "C42") (pin "1") (pinfunction "1_1") (pintype "passive"))
      (node (ref "C8") (pin "1") (pinfunction "1_1") (pintype "passive"))
      (node (ref "D1") (pin "A") (pinfunction "A_A") (pintype "passive"))
      (node (ref "IC17") (pin "14") (pinfunction "VCC_14") (pintype "bidirectional"))
      (node (ref "IC18") (pin "14") (pinfunction "VCC_14") (pintype "bidirectional"))
      (node (ref "IC19") (pin "14") (pinfunction "VCC_14") (pintype "bidirectional"))
      (node (ref "IC20") (pin "14") (pinfunction "VCC_14") (pintype "bidirectional"))
      (node (ref "IC21") (pin "14") (pinfunction "VCC_14") (pintype "bidirectional"))
      (node (ref "IC22") (pin "14") (pinfunction "VCC_14") (pintype "bidirectional"))
      (node (ref "IC23") (pin "14") (pinfunction "VCC_14") (pintype "bidirectional"))
      (node (ref "IC24") (pin "14") (pinfunction "VCC_14") (pintype "bidirectional"))
      (node (ref "IC25") (pin "14") (pinfunction "VCC_14") (pintype "bidirectional"))
      (node (ref "IC26") (pin "14") (pinfunction "VCC_14") (pintype "bidirectional"))
      (node (ref "IC27") (pin "14") (pinfunction "VCC_14") (pintype "bidirectional"))
      (node (ref "IC28") (pin "14") (pinfunction "VCC_14") (pintype "bidirectional"))
      (node (ref "L1") (pin "1") (pinfunction "2_1") (pintype "passive"))
      (node (ref "R18") (pin "1") (pinfunction "1_1") (pintype "passive"))
    )
    (net (code "80") (name "unconnected-(CON1-Pad1)") (class "Default")
      (node (ref "CON1") (pin "1") (pinfunction "1_1") (pintype "passive"))
    )
    (net (code "81") (name "unconnected-(CON1-Pad2)") (class "Default")
      (node (ref "CON1") (pin "2") (pinfunction "2_2") (pintype "passive"))
    )
    (net (code "82") (name "unconnected-(CON1-Pad3)") (class "Default")
      (node (ref "CON1") (pin "3") (pinfunction "3_3") (pintype "passive"))
    )
    (net (code "83") (name "unconnected-(CON1-Pad5)") (class "Default")
      (node (ref "CON1") (pin "5") (pinfunction "5_5") (pintype "passive"))
    )
    (net (code "84") (name "unconnected-(CON1-Pad6)") (class "Default")
      (node (ref "CON1") (pin "6") (pinfunction "6_6") (pintype "passive"))
    )
    (net (code "85") (name "unconnected-(CON1-Pad7)") (class "Default")
      (node (ref "CON1") (pin "7") (pinfunction "7_7") (pintype "passive"))
    )
    (net (code "86") (name "unconnected-(CON1-Pad10)") (class "Default")
      (node (ref "CON1") (pin "10") (pinfunction "10_10") (pintype "passive"))
    )
    (net (code "87") (name "unconnected-(CON1-Pad13)") (class "Default")
      (node (ref "CON1") (pin "13") (pinfunction "13_13") (pintype "passive"))
    )
    (net (code "88") (name "unconnected-(CON1-Pad16)") (class "Default")
      (node (ref "CON1") (pin "16") (pinfunction "16_16") (pintype "passive"))
    )
    (net (code "89") (name "unconnected-(IC2-NC-Pad7)") (class "Default")
      (node (ref "IC2") (pin "7") (pinfunction "NC_7") (pintype "no_connect"))
    )
    (net (code "90") (name "unconnected-(IC16-ADC6-Pad19)") (class "Default")
      (node (ref "IC16") (pin "19") (pinfunction "ADC6_19") (pintype "bidirectional"))
    )
    (net (code "91") (name "unconnected-(IC16-ADC7-Pad22)") (class "Default")
      (node (ref "IC16") (pin "22") (pinfunction "ADC7_22") (pintype "bidirectional"))
    )
    (net (code "92") (name "unconnected-(IC16-AREF-Pad20)") (class "Default")
      (node (ref "IC16") (pin "20") (pinfunction "AREF_20") (pintype "passive"))
    )
    (net (code "93") (name "unconnected-(IC16-PD5(T1)-Pad9)") (class "Default")
      (node (ref "IC16") (pin "9") (pinfunction "PD5(T1)_9") (pintype "bidirectional"))
    )
    (net (code "94") (name "unconnected-(IC17-C1N-Pad4)") (class "Default")
      (node (ref "IC17") (pin "4") (pinfunction "C1N_4") (pintype "bidirectional"))
    )
    (net (code "95") (name "unconnected-(IC17-C1P-Pad3)") (class "Default")
      (node (ref "IC17") (pin "3") (pinfunction "C1P_3") (pintype "bidirectional"))
    )
    (net (code "96") (name "unconnected-(IC17-C2N-Pad2)") (class "Default")
      (node (ref "IC17") (pin "2") (pinfunction "C2N_2") (pintype "bidirectional"))
    )
    (net (code "97") (name "unconnected-(IC17-C2P-Pad1)") (class "Default")
      (node (ref "IC17") (pin "1") (pinfunction "C2P_1") (pintype "bidirectional"))
    )
    (net (code "98") (name "unconnected-(IC17-VBREF-Pad6)") (class "Default")
      (node (ref "IC17") (pin "6") (pinfunction "VBREF_6") (pintype "bidirectional"))
    )
    (net (code "99") (name "unconnected-(IC18-C1N-Pad4)") (class "Default")
      (node (ref "IC18") (pin "4") (pinfunction "C1N_4") (pintype "bidirectional"))
    )
    (net (code "100") (name "unconnected-(IC18-C1P-Pad3)") (class "Default")
      (node (ref "IC18") (pin "3") (pinfunction "C1P_3") (pintype "bidirectional"))
    )
    (net (code "101") (name "unconnected-(IC18-C2N-Pad2)") (class "Default")
      (node (ref "IC18") (pin "2") (pinfunction "C2N_2") (pintype "bidirectional"))
    )
    (net (code "102") (name "unconnected-(IC18-C2P-Pad1)") (class "Default")
      (node (ref "IC18") (pin "1") (pinfunction "C2P_1") (pintype "bidirectional"))
    )
    (net (code "103") (name "unconnected-(IC18-VBREF-Pad6)") (class "Default")
      (node (ref "IC18") (pin "6") (pinfunction "VBREF_6") (pintype "bidirectional"))
    )
    (net (code "104") (name "unconnected-(IC19-C1N-Pad4)") (class "Default")
      (node (ref "IC19") (pin "4") (pinfunction "C1N_4") (pintype "bidirectional"))
    )
    (net (code "105") (name "unconnected-(IC19-C1P-Pad3)") (class "Default")
      (node (ref "IC19") (pin "3") (pinfunction "C1P_3") (pintype "bidirectional"))
    )
    (net (code "106") (name "unconnected-(IC19-C2N-Pad2)") (class "Default")
      (node (ref "IC19") (pin "2") (pinfunction "C2N_2") (pintype "bidirectional"))
    )
    (net (code "107") (name "unconnected-(IC19-C2P-Pad1)") (class "Default")
      (node (ref "IC19") (pin "1") (pinfunction "C2P_1") (pintype "bidirectional"))
    )
    (net (code "108") (name "unconnected-(IC19-VBREF-Pad6)") (class "Default")
      (node (ref "IC19") (pin "6") (pinfunction "VBREF_6") (pintype "bidirectional"))
    )
    (net (code "109") (name "unconnected-(IC20-C1N-Pad4)") (class "Default")
      (node (ref "IC20") (pin "4") (pinfunction "C1N_4") (pintype "bidirectional"))
    )
    (net (code "110") (name "unconnected-(IC20-C1P-Pad3)") (class "Default")
      (node (ref "IC20") (pin "3") (pinfunction "C1P_3") (pintype "bidirectional"))
    )
    (net (code "111") (name "unconnected-(IC20-C2N-Pad2)") (class "Default")
      (node (ref "IC20") (pin "2") (pinfunction "C2N_2") (pintype "bidirectional"))
    )
    (net (code "112") (name "unconnected-(IC20-C2P-Pad1)") (class "Default")
      (node (ref "IC20") (pin "1") (pinfunction "C2P_1") (pintype "bidirectional"))
    )
    (net (code "113") (name "unconnected-(IC20-VBREF-Pad6)") (class "Default")
      (node (ref "IC20") (pin "6") (pinfunction "VBREF_6") (pintype "bidirectional"))
    )
    (net (code "114") (name "unconnected-(IC21-C1N-Pad4)") (class "Default")
      (node (ref "IC21") (pin "4") (pinfunction "C1N_4") (pintype "bidirectional"))
    )
    (net (code "115") (name "unconnected-(IC21-C1P-Pad3)") (class "Default")
      (node (ref "IC21") (pin "3") (pinfunction "C1P_3") (pintype "bidirectional"))
    )
    (net (code "116") (name "unconnected-(IC21-C2N-Pad2)") (class "Default")
      (node (ref "IC21") (pin "2") (pinfunction "C2N_2") (pintype "bidirectional"))
    )
    (net (code "117") (name "unconnected-(IC21-C2P-Pad1)") (class "Default")
      (node (ref "IC21") (pin "1") (pinfunction "C2P_1") (pintype "bidirectional"))
    )
    (net (code "118") (name "unconnected-(IC21-VBREF-Pad6)") (class "Default")
      (node (ref "IC21") (pin "6") (pinfunction "VBREF_6") (pintype "bidirectional"))
    )
    (net (code "119") (name "unconnected-(IC22-C1N-Pad4)") (class "Default")
      (node (ref "IC22") (pin "4") (pinfunction "C1N_4") (pintype "bidirectional"))
    )
    (net (code "120") (name "unconnected-(IC22-C1P-Pad3)") (class "Default")
      (node (ref "IC22") (pin "3") (pinfunction "C1P_3") (pintype "bidirectional"))
    )
    (net (code "121") (name "unconnected-(IC22-C2N-Pad2)") (class "Default")
      (node (ref "IC22") (pin "2") (pinfunction "C2N_2") (pintype "bidirectional"))
    )
    (net (code "122") (name "unconnected-(IC22-C2P-Pad1)") (class "Default")
      (node (ref "IC22") (pin "1") (pinfunction "C2P_1") (pintype "bidirectional"))
    )
    (net (code "123") (name "unconnected-(IC22-VBREF-Pad6)") (class "Default")
      (node (ref "IC22") (pin "6") (pinfunction "VBREF_6") (pintype "bidirectional"))
    )
    (net (code "124") (name "unconnected-(IC23-C1N-Pad4)") (class "Default")
      (node (ref "IC23") (pin "4") (pinfunction "C1N_4") (pintype "bidirectional"))
    )
    (net (code "125") (name "unconnected-(IC23-C1P-Pad3)") (class "Default")
      (node (ref "IC23") (pin "3") (pinfunction "C1P_3") (pintype "bidirectional"))
    )
    (net (code "126") (name "unconnected-(IC23-C2N-Pad2)") (class "Default")
      (node (ref "IC23") (pin "2") (pinfunction "C2N_2") (pintype "bidirectional"))
    )
    (net (code "127") (name "unconnected-(IC23-C2P-Pad1)") (class "Default")
      (node (ref "IC23") (pin "1") (pinfunction "C2P_1") (pintype "bidirectional"))
    )
    (net (code "128") (name "unconnected-(IC23-VBREF-Pad6)") (class "Default")
      (node (ref "IC23") (pin "6") (pinfunction "VBREF_6") (pintype "bidirectional"))
    )
    (net (code "129") (name "unconnected-(IC24-C1N-Pad4)") (class "Default")
      (node (ref "IC24") (pin "4") (pinfunction "C1N_4") (pintype "bidirectional"))
    )
    (net (code "130") (name "unconnected-(IC24-C1P-Pad3)") (class "Default")
      (node (ref "IC24") (pin "3") (pinfunction "C1P_3") (pintype "bidirectional"))
    )
    (net (code "131") (name "unconnected-(IC24-C2N-Pad2)") (class "Default")
      (node (ref "IC24") (pin "2") (pinfunction "C2N_2") (pintype "bidirectional"))
    )
    (net (code "132") (name "unconnected-(IC24-C2P-Pad1)") (class "Default")
      (node (ref "IC24") (pin "1") (pinfunction "C2P_1") (pintype "bidirectional"))
    )
    (net (code "133") (name "unconnected-(IC24-VBREF-Pad6)") (class "Default")
      (node (ref "IC24") (pin "6") (pinfunction "VBREF_6") (pintype "bidirectional"))
    )
    (net (code "134") (name "unconnected-(IC25-C1N-Pad4)") (class "Default")
      (node (ref "IC25") (pin "4") (pinfunction "C1N_4") (pintype "bidirectional"))
    )
    (net (code "135") (name "unconnected-(IC25-C1P-Pad3)") (class "Default")
      (node (ref "IC25") (pin "3") (pinfunction "C1P_3") (pintype "bidirectional"))
    )
    (net (code "136") (name "unconnected-(IC25-C2N-Pad2)") (class "Default")
      (node (ref "IC25") (pin "2") (pinfunction "C2N_2") (pintype "bidirectional"))
    )
    (net (code "137") (name "unconnected-(IC25-C2P-Pad1)") (class "Default")
      (node (ref "IC25") (pin "1") (pinfunction "C2P_1") (pintype "bidirectional"))
    )
    (net (code "138") (name "unconnected-(IC25-VBREF-Pad6)") (class "Default")
      (node (ref "IC25") (pin "6") (pinfunction "VBREF_6") (pintype "bidirectional"))
    )
    (net (code "139") (name "unconnected-(IC26-C1N-Pad4)") (class "Default")
      (node (ref "IC26") (pin "4") (pinfunction "C1N_4") (pintype "bidirectional"))
    )
    (net (code "140") (name "unconnected-(IC26-C1P-Pad3)") (class "Default")
      (node (ref "IC26") (pin "3") (pinfunction "C1P_3") (pintype "bidirectional"))
    )
    (net (code "141") (name "unconnected-(IC26-C2N-Pad2)") (class "Default")
      (node (ref "IC26") (pin "2") (pinfunction "C2N_2") (pintype "bidirectional"))
    )
    (net (code "142") (name "unconnected-(IC26-C2P-Pad1)") (class "Default")
      (node (ref "IC26") (pin "1") (pinfunction "C2P_1") (pintype "bidirectional"))
    )
    (net (code "143") (name "unconnected-(IC26-VBREF-Pad6)") (class "Default")
      (node (ref "IC26") (pin "6") (pinfunction "VBREF_6") (pintype "bidirectional"))
    )
    (net (code "144") (name "unconnected-(IC27-C1N-Pad4)") (class "Default")
      (node (ref "IC27") (pin "4") (pinfunction "C1N_4") (pintype "bidirectional"))
    )
    (net (code "145") (name "unconnected-(IC27-C1P-Pad3)") (class "Default")
      (node (ref "IC27") (pin "3") (pinfunction "C1P_3") (pintype "bidirectional"))
    )
    (net (code "146") (name "unconnected-(IC27-C2N-Pad2)") (class "Default")
      (node (ref "IC27") (pin "2") (pinfunction "C2N_2") (pintype "bidirectional"))
    )
    (net (code "147") (name "unconnected-(IC27-C2P-Pad1)") (class "Default")
      (node (ref "IC27") (pin "1") (pinfunction "C2P_1") (pintype "bidirectional"))
    )
    (net (code "148") (name "unconnected-(IC27-VBREF-Pad6)") (class "Default")
      (node (ref "IC27") (pin "6") (pinfunction "VBREF_6") (pintype "bidirectional"))
    )
    (net (code "149") (name "unconnected-(IC28-C1N-Pad4)") (class "Default")
      (node (ref "IC28") (pin "4") (pinfunction "C1N_4") (pintype "bidirectional"))
    )
    (net (code "150") (name "unconnected-(IC28-C1P-Pad3)") (class "Default")
      (node (ref "IC28") (pin "3") (pinfunction "C1P_3") (pintype "bidirectional"))
    )
    (net (code "151") (name "unconnected-(IC28-C2N-Pad2)") (class "Default")
      (node (ref "IC28") (pin "2") (pinfunction "C2N_2") (pintype "bidirectional"))
    )
    (net (code "152") (name "unconnected-(IC28-C2P-Pad1)") (class "Default")
      (node (ref "IC28") (pin "1") (pinfunction "C2P_1") (pintype "bidirectional"))
    )
    (net (code "153") (name "unconnected-(IC28-VBREF-Pad6)") (class "Default")
      (node (ref "IC28") (pin "6") (pinfunction "VBREF_6") (pintype "bidirectional"))
    )
    (net (code "154") (name "unconnected-(JP5'-Pad1)") (class "Default")
      (node (ref "JP5'") (pin "1") (pinfunction "1_1") (pintype "passive"))
    )
    (net (code "155") (name "unconnected-(JP7-Pad1)") (class "Default")
      (node (ref "JP7") (pin "1") (pinfunction "1_1") (pintype "passive"))
    )
  )
)
